# Schematic2.net
KiCad netlist of a schematic drawn in Altium Designer
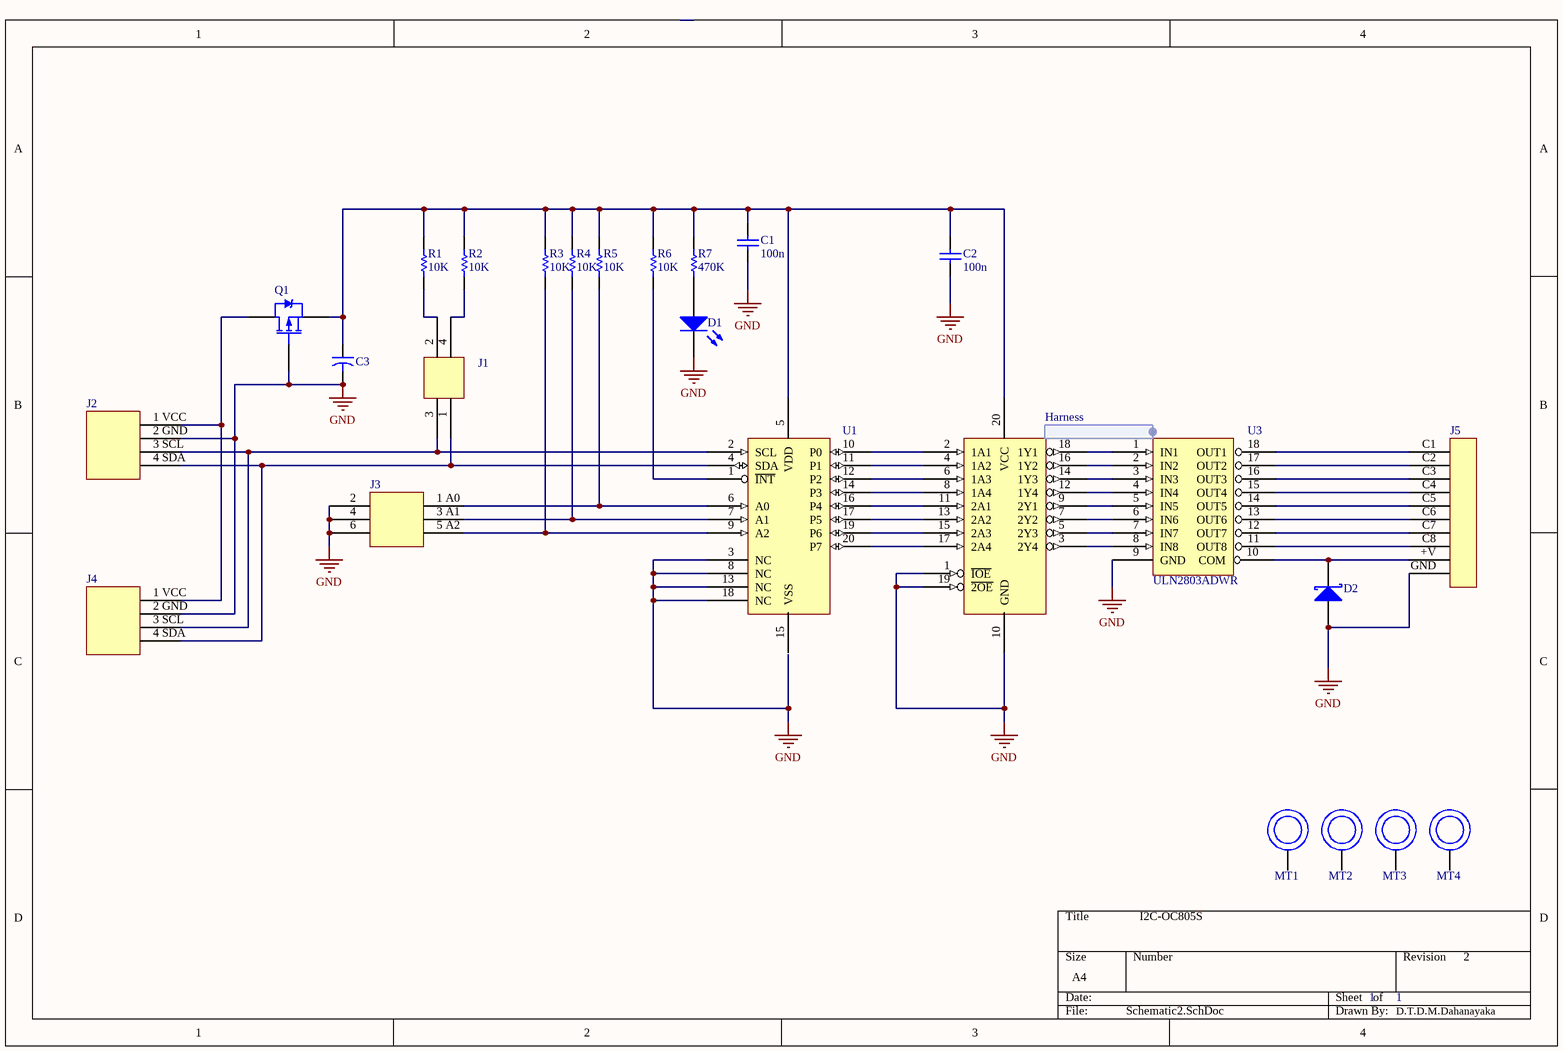
[diagram p0: Schematic2.SchDoc]

(export (version "E")
  (design (tool "Eeschema 10.0.6"))
  (components
    (comp (ref "*") (value "U1") (libsource (lib "U1") (part "Component_1")))
    (comp (ref "C1")
      (value "100n")
      (footprint "RAD-0.3")
      (description "Capacitor")
      (fields (field (name "Comment") "Cap") (field (name "PUBLISHER") "Altium Limited"))
      (libsource (lib "Miscellaneous Devices") (part "Cap"))
    )
    (comp (ref "C2")
      (value "100n")
      (footprint "RAD-0.3")
      (description "Capacitor")
      (fields (field (name "Comment") "Cap") (field (name "PUBLISHER") "Altium Limited"))
      (libsource (lib "Miscellaneous Devices") (part "Cap"))
    )
    (comp (ref "C3")
      (value "Cap2")
      (footprint "CAPR5-4X5")
      (description "Capacitor")
      (fields (field (name "PUBLISHER") "Altium Limited"))
      (libsource (lib "Miscellaneous Devices") (part "Cap2"))
    )
    (comp (ref "D1")
      (value "LED1")
      (footprint "LED-1")
      (description "Typical RED GaAs LED")
      (fields (field (name "PUBLISHER") "Altium Limited"))
      (libsource (lib "Miscellaneous Devices") (part "LED1"))
    )
    (comp (ref "D2")
      (value "Diode 10TQ035")
      (footprint "TO-220AC")
      (description "Schottky Rectifier")
      (fields (field (name "PUBLISHER") "Altium Limited"))
      (libsource (lib "Miscellaneous Devices") (part "Diode 10TQ035"))
    )
    (comp (ref "J1") (value "Component_1") (libsource (lib "J3") (part "Component_1")))
    (comp (ref "J2") (value "Component_1") (libsource (lib "J1") (part "Component_1")))
    (comp (ref "J3") (value "Component_1") (libsource (lib "J2") (part "Component_1")))
    (comp (ref "J4") (value "Component_1") (libsource (lib "J1") (part "Component_1")))
    (comp (ref "J5") (value "Component_1") (libsource (lib "connector8") (part "Component_1")))
    (comp (ref "MT1") (value "Component_1") (libsource (lib "mt") (part "Component_1")))
    (comp (ref "MT2") (value "~") (libsource (lib "mt") (part "Component_1")))
    (comp (ref "MT3") (value "~") (libsource (lib "mt") (part "Component_1")))
    (comp (ref "MT4") (value "~") (libsource (lib "mt") (part "Component_1")))
    (comp (ref "Q1")
      (value "PMOS-2")
      (footprint "TO-220AB")
      (description "P-Channel Power MOSFET")
      (fields (field (name "PUBLISHER") "Altium Limited"))
      (libsource (lib "Miscellaneous Devices") (part "PMOS-2"))
    )
    (comp (ref "R1")
      (value "10K")
      (footprint "AXIAL-0.3")
      (description "Resistor")
      (fields (field (name "PUBLISHER") "Altium Limited"))
      (libsource (lib "Miscellaneous Devices") (part "Res1"))
    )
    (comp (ref "R2")
      (value "10K")
      (footprint "AXIAL-0.3")
      (description "Resistor")
      (fields (field (name "PUBLISHER") "Altium Limited"))
      (libsource (lib "Miscellaneous Devices") (part "Res1"))
    )
    (comp (ref "R3")
      (value "10K")
      (footprint "AXIAL-0.3")
      (description "Resistor")
      (fields (field (name "PUBLISHER") "Altium Limited"))
      (libsource (lib "Miscellaneous Devices") (part "Res1"))
    )
    (comp (ref "R4")
      (value "10K")
      (footprint "AXIAL-0.3")
      (description "Resistor")
      (fields (field (name "PUBLISHER") "Altium Limited"))
      (libsource (lib "Miscellaneous Devices") (part "Res1"))
    )
    (comp (ref "R5")
      (value "10K")
      (footprint "AXIAL-0.3")
      (description "Resistor")
      (fields (field (name "PUBLISHER") "Altium Limited"))
      (libsource (lib "Miscellaneous Devices") (part "Res1"))
    )
    (comp (ref "R6")
      (value "10K")
      (footprint "AXIAL-0.3")
      (description "Resistor")
      (fields (field (name "PUBLISHER") "Altium Limited"))
      (libsource (lib "Miscellaneous Devices") (part "Res1"))
    )
    (comp (ref "R7")
      (value "470K")
      (footprint "AXIAL-0.3")
      (description "Resistor")
      (fields (field (name "PUBLISHER") "Altium Limited"))
      (libsource (lib "Miscellaneous Devices") (part "Res1"))
    )
    (comp (ref "U2") (value "~") (libsource (lib "U2") (part "Component_1")))
    (comp (ref "U3") (value "ULN2803ADWR") (libsource (lib "ULN2803ADWR") (part "Component_1")))
  )
  (nets
    (net (code "1") (name "GND") (class "Default")
      (node (ref "*") (pin "13") (pinfunction "NC_13") (pintype "passive"))
      (node (ref "*") (pin "18") (pinfunction "NC_18") (pintype "passive"))
      (node (ref "*") (pin "3") (pinfunction "NC_3") (pintype "passive"))
      (node (ref "*") (pin "8") (pinfunction "NC_8") (pintype "passive"))
      (node (ref "C1") (pin "2") (pinfunction "2_2") (pintype "passive"))
      (node (ref "C2") (pin "2") (pinfunction "2_2") (pintype "passive"))
      (node (ref "C3") (pin "2") (pinfunction "2_2") (pintype "passive"))
      (node (ref "D1") (pin "2") (pinfunction "K_2") (pintype "passive"))
      (node (ref "D2") (pin "3") (pinfunction "A_3") (pintype "passive"))
      (node (ref "J2") (pin "2_GND") (pintype "passive"))
      (node (ref "J3") (pin "2") (pintype "passive"))
      (node (ref "J3") (pin "4") (pintype "passive"))
      (node (ref "J3") (pin "6") (pintype "passive"))
      (node (ref "J4") (pin "2_GND") (pintype "passive"))
      (node (ref "J5") (pin "GND") (pintype "passive"))
      (node (ref "Q1") (pin "1") (pinfunction "G_1") (pintype "passive"))
      (node (ref "U2") (pin "1") (pinfunction "~{IOE}_1") (pintype "input"))
      (node (ref "U2") (pin "10") (pinfunction "GND_10") (pintype "passive"))
      (node (ref "U2") (pin "19") (pinfunction "~{2OE}_19") (pintype "input"))
      (node (ref "U3") (pin "9") (pinfunction "GND_9") (pintype "passive"))
    )
    (net (code "2") (name "Net-(*-A0)") (class "Default")
      (node (ref "*") (pin "6") (pinfunction "A0_6") (pintype "input"))
      (node (ref "J3") (pin "1_A0") (pintype "passive"))
      (node (ref "R5") (pin "1") (pinfunction "1_1") (pintype "passive"))
    )
    (net (code "3") (name "Net-(*-A1)") (class "Default")
      (node (ref "*") (pin "7") (pinfunction "A1_7") (pintype "input"))
      (node (ref "J3") (pin "3_A1") (pintype "passive"))
      (node (ref "R4") (pin "1") (pinfunction "1_1") (pintype "passive"))
    )
    (net (code "4") (name "Net-(*-A2)") (class "Default")
      (node (ref "*") (pin "9") (pinfunction "A2_9") (pintype "input"))
      (node (ref "J3") (pin "5_A2") (pintype "passive"))
      (node (ref "R3") (pin "1") (pinfunction "1_1") (pintype "passive"))
    )
    (net (code "5") (name "Net-(*-P0)") (class "Default")
      (node (ref "*") (pin "10") (pinfunction "P0_10") (pintype "bidirectional"))
      (node (ref "U2") (pin "2") (pinfunction "1A1_2") (pintype "input"))
    )
    (net (code "6") (name "Net-(*-P1)") (class "Default")
      (node (ref "*") (pin "11") (pinfunction "P1_11") (pintype "bidirectional"))
      (node (ref "U2") (pin "4") (pinfunction "1A2_4") (pintype "input"))
    )
    (net (code "7") (name "Net-(*-P2)") (class "Default")
      (node (ref "*") (pin "12") (pinfunction "P2_12") (pintype "bidirectional"))
      (node (ref "U2") (pin "6") (pinfunction "1A3_6") (pintype "input"))
    )
    (net (code "8") (name "Net-(*-P3)") (class "Default")
      (node (ref "*") (pin "14") (pinfunction "P3_14") (pintype "bidirectional"))
      (node (ref "U2") (pin "8") (pinfunction "1A4_8") (pintype "input"))
    )
    (net (code "9") (name "Net-(*-P4)") (class "Default")
      (node (ref "*") (pin "16") (pinfunction "P4_16") (pintype "bidirectional"))
      (node (ref "U2") (pin "11") (pinfunction "2A1_11") (pintype "input"))
    )
    (net (code "10") (name "Net-(*-P5)") (class "Default")
      (node (ref "*") (pin "17") (pinfunction "P5_17") (pintype "bidirectional"))
      (node (ref "U2") (pin "13") (pinfunction "2A2_13") (pintype "input"))
    )
    (net (code "11") (name "Net-(*-P6)") (class "Default")
      (node (ref "*") (pin "19") (pinfunction "P6_19") (pintype "bidirectional"))
      (node (ref "U2") (pin "15") (pinfunction "2A3_15") (pintype "input"))
    )
    (net (code "12") (name "Net-(*-P7)") (class "Default")
      (node (ref "*") (pin "20") (pinfunction "P7_20") (pintype "bidirectional"))
      (node (ref "U2") (pin "17") (pinfunction "2A4_17") (pintype "input"))
    )
    (net (code "13") (name "Net-(*-SCL)") (class "Default")
      (node (ref "*") (pin "2") (pinfunction "SCL_2") (pintype "input"))
      (node (ref "J1") (pin "3") (pintype "passive"))
      (node (ref "J2") (pin "3_SCL") (pintype "passive"))
      (node (ref "J4") (pin "3_SCL") (pintype "passive"))
    )
    (net (code "14") (name "Net-(*-SDA)") (class "Default")
      (node (ref "*") (pin "4") (pinfunction "SDA_4") (pintype "bidirectional"))
      (node (ref "J1") (pin "1") (pintype "passive"))
      (node (ref "J2") (pin "4_SDA") (pintype "passive"))
      (node (ref "J4") (pin "4_SDA") (pintype "passive"))
    )
    (net (code "15") (name "Net-(*-VDD)") (class "Default")
      (node (ref "*") (pin "5") (pinfunction "VDD_5") (pintype "passive"))
      (node (ref "C1") (pin "1") (pinfunction "1_1") (pintype "passive"))
      (node (ref "C2") (pin "1") (pinfunction "1_1") (pintype "passive"))
      (node (ref "C3") (pin "1") (pinfunction "1_1") (pintype "passive"))
      (node (ref "Q1") (pin "3") (pinfunction "S_3") (pintype "passive"))
      (node (ref "R1") (pin "2") (pinfunction "2_2") (pintype "passive"))
      (node (ref "R2") (pin "2") (pinfunction "2_2") (pintype "passive"))
      (node (ref "R3") (pin "2") (pinfunction "2_2") (pintype "passive"))
      (node (ref "R4") (pin "2") (pinfunction "2_2") (pintype "passive"))
      (node (ref "R5") (pin "2") (pinfunction "2_2") (pintype "passive"))
      (node (ref "R6") (pin "2") (pinfunction "2_2") (pintype "passive"))
      (node (ref "R7") (pin "2") (pinfunction "2_2") (pintype "passive"))
      (node (ref "U2") (pin "20") (pinfunction "VCC_20") (pintype "passive"))
    )
    (net (code "16") (name "Net-(*-~{INT})") (class "Default")
      (node (ref "*") (pin "1") (pinfunction "~{INT}_1") (pintype "passive"))
      (node (ref "R6") (pin "1") (pinfunction "1_1") (pintype "passive"))
    )
    (net (code "17") (name "Net-(D1-A)") (class "Default")
      (node (ref "D1") (pin "1") (pinfunction "A_1") (pintype "passive"))
      (node (ref "R7") (pin "1") (pinfunction "1_1") (pintype "passive"))
    )
    (net (code "18") (name "Net-(D2-K)") (class "Default")
      (node (ref "D2") (pin "1") (pinfunction "K_1") (pintype "passive"))
      (node (ref "J5") (pin "+V") (pintype "passive"))
      (node (ref "U3") (pin "10") (pinfunction "COM_10") (pintype "passive"))
    )
    (net (code "19") (name "Net-(J1-Pad2)") (class "Default")
      (node (ref "J1") (pin "2") (pintype "passive"))
      (node (ref "R1") (pin "1") (pinfunction "1_1") (pintype "passive"))
    )
    (net (code "20") (name "Net-(J1-Pad4)") (class "Default")
      (node (ref "J1") (pin "4") (pintype "passive"))
      (node (ref "R2") (pin "1") (pinfunction "1_1") (pintype "passive"))
    )
    (net (code "21") (name "Net-(Q1-D)") (class "Default")
      (node (ref "J2") (pin "1_VCC") (pintype "passive"))
      (node (ref "J4") (pin "1_VCC") (pintype "passive"))
      (node (ref "Q1") (pin "2") (pinfunction "D_2") (pintype "passive"))
    )
    (net (code "22") (name "Net-(U2-1Y1)") (class "Default")
      (node (ref "U2") (pin "18") (pinfunction "1Y1_18") (pintype "output"))
      (node (ref "U3") (pin "1") (pinfunction "IN1_1") (pintype "input"))
    )
    (net (code "23") (name "Net-(U2-1Y2)") (class "Default")
      (node (ref "U2") (pin "16") (pinfunction "1Y2_16") (pintype "output"))
      (node (ref "U3") (pin "2") (pinfunction "IN2_2") (pintype "input"))
    )
    (net (code "24") (name "Net-(U2-1Y3)") (class "Default")
      (node (ref "U2") (pin "14") (pinfunction "1Y3_14") (pintype "output"))
      (node (ref "U3") (pin "3") (pinfunction "IN3_3") (pintype "input"))
    )
    (net (code "25") (name "Net-(U2-1Y4)") (class "Default")
      (node (ref "U2") (pin "12") (pinfunction "1Y4_12") (pintype "output"))
      (node (ref "U3") (pin "4") (pinfunction "IN4_4") (pintype "input"))
    )
    (net (code "26") (name "Net-(U2-2Y1)") (class "Default")
      (node (ref "U2") (pin "9") (pinfunction "2Y1_9") (pintype "output"))
      (node (ref "U3") (pin "5") (pinfunction "IN5_5") (pintype "input"))
    )
    (net (code "27") (name "Net-(U2-2Y2)") (class "Default")
      (node (ref "U2") (pin "7") (pinfunction "2Y2_7") (pintype "output"))
      (node (ref "U3") (pin "6") (pinfunction "IN6_6") (pintype "input"))
    )
    (net (code "28") (name "Net-(U2-2Y3)") (class "Default")
      (node (ref "U2") (pin "5") (pinfunction "2Y3_5") (pintype "output"))
      (node (ref "U3") (pin "7") (pinfunction "IN7_7") (pintype "input"))
    )
    (net (code "29") (name "Net-(U2-2Y4)") (class "Default")
      (node (ref "U2") (pin "3") (pinfunction "2Y4_3") (pintype "output"))
      (node (ref "U3") (pin "8") (pinfunction "IN8_8") (pintype "input"))
    )
    (net (code "30") (name "Net-(U3-OUT1)") (class "Default")
      (node (ref "J5") (pin "C1") (pintype "passive"))
      (node (ref "U3") (pin "18") (pinfunction "OUT1_18") (pintype "passive"))
    )
    (net (code "31") (name "Net-(U3-OUT2)") (class "Default")
      (node (ref "J5") (pin "C2") (pintype "passive"))
      (node (ref "U3") (pin "17") (pinfunction "OUT2_17") (pintype "passive"))
    )
    (net (code "32") (name "Net-(U3-OUT3)") (class "Default")
      (node (ref "J5") (pin "C3") (pintype "passive"))
      (node (ref "U3") (pin "16") (pinfunction "OUT3_16") (pintype "passive"))
    )
    (net (code "33") (name "Net-(U3-OUT4)") (class "Default")
      (node (ref "J5") (pin "C4") (pintype "passive"))
      (node (ref "U3") (pin "15") (pinfunction "OUT4_15") (pintype "passive"))
    )
    (net (code "34") (name "Net-(U3-OUT5)") (class "Default")
      (node (ref "J5") (pin "C5") (pintype "passive"))
      (node (ref "U3") (pin "14") (pinfunction "OUT5_14") (pintype "passive"))
    )
    (net (code "35") (name "Net-(U3-OUT6)") (class "Default")
      (node (ref "J5") (pin "C6") (pintype "passive"))
      (node (ref "U3") (pin "13") (pinfunction "OUT6_13") (pintype "passive"))
    )
    (net (code "36") (name "Net-(U3-OUT7)") (class "Default")
      (node (ref "J5") (pin "C7") (pintype "passive"))
      (node (ref "U3") (pin "12") (pinfunction "OUT7_12") (pintype "passive"))
    )
    (net (code "37") (name "Net-(U3-OUT8)") (class "Default")
      (node (ref "J5") (pin "C8") (pintype "passive"))
      (node (ref "U3") (pin "11") (pinfunction "OUT8_11") (pintype "passive"))
    )
    (net (code "38") (name "unconnected-(*-VSS-Pad15)") (class "Default")
      (node (ref "*") (pin "15") (pinfunction "VSS_15") (pintype "passive"))
    )
    (net (code "39") (name "unconnected-(MT1-Pad)") (class "Default")
      (node (ref "MT1") (pin "") (pintype "power_in"))
    )
    (net (code "40") (name "unconnected-(MT2-Pad)") (class "Default")
      (node (ref "MT2") (pin "") (pintype "power_in"))
    )
    (net (code "41") (name "unconnected-(MT3-Pad)") (class "Default")
      (node (ref "MT3") (pin "") (pintype "power_in"))
    )
    (net (code "42") (name "unconnected-(MT4-Pad)") (class "Default")
      (node (ref "MT4") (pin "") (pintype "power_in"))
    )
  )
)
